# processor_beaglebone.net
KiCad netlist of a schematic drawn in Altium Designer
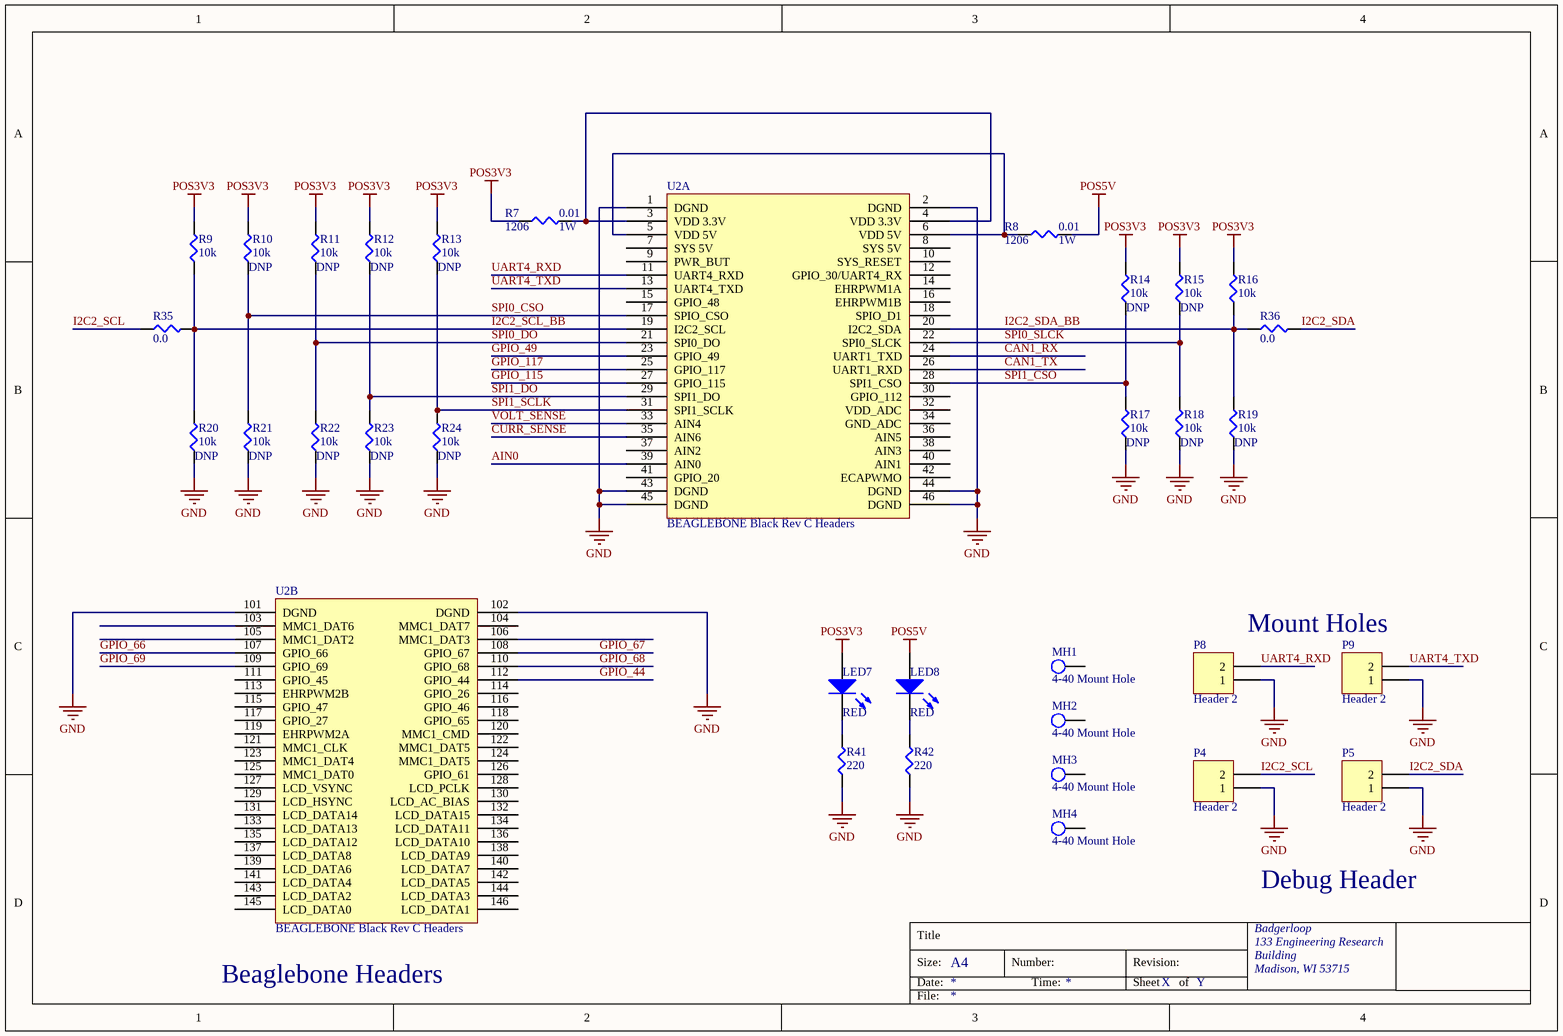
[diagram p0: processor_beaglebone.SchDoc]

(export (version "E")
  (design (tool "Eeschema 10.0.6"))
  (components
    (comp (ref "LED7")
      (value "RED")
      (footprint "LED 0603 RED")
      (description "Red 631nm LED Indication - Discrete 2V 0603 (1608 Metric)")
      (fields (field (name "MANUFACTURER") "Lite-On Inc."))
      (libsource (lib "misc") (part "LED RED 0603"))
    )
    (comp (ref "LED8")
      (value "RED")
      (footprint "LED 0603 RED")
      (description "Red 631nm LED Indication - Discrete 2V 0603 (1608 Metric)")
      (fields (field (name "MANUFACTURER") "Lite-On Inc."))
      (libsource (lib "misc") (part "LED RED 0603"))
    )
    (comp (ref "MH1")
      (value "4-40 Mount Hole")
      (footprint "MH")
      (libsource (lib "misc") (part "4-40 Mount Hole"))
    )
    (comp (ref "MH2")
      (value "4-40 Mount Hole")
      (footprint "MH")
      (libsource (lib "misc") (part "4-40 Mount Hole"))
    )
    (comp (ref "MH3")
      (value "4-40 Mount Hole")
      (footprint "MH")
      (libsource (lib "misc") (part "4-40 Mount Hole"))
    )
    (comp (ref "MH4")
      (value "4-40 Mount Hole")
      (footprint "MH")
      (libsource (lib "misc") (part "4-40 Mount Hole"))
    )
    (comp (ref "P4")
      (value "Header 2")
      (footprint "Pin Header 1x2 TH Pitch 2.54mm")
      (description "Header, 2-Pin")
      (fields (field (name "PUBLISHER") "Altium Limited"))
      (libsource (lib "connector") (part "Header 2"))
    )
    (comp (ref "P5")
      (value "Header 2")
      (footprint "Pin Header 1x2 TH Pitch 2.54mm")
      (description "Header, 2-Pin")
      (fields (field (name "PUBLISHER") "Altium Limited"))
      (libsource (lib "connector") (part "Header 2"))
    )
    (comp (ref "P8")
      (value "Header 2")
      (footprint "Pin Header 1x2 TH Pitch 2.54mm")
      (description "Header, 2-Pin")
      (fields (field (name "PUBLISHER") "Altium Limited"))
      (libsource (lib "connector") (part "Header 2"))
    )
    (comp (ref "P9")
      (value "Header 2")
      (footprint "Pin Header 1x2 TH Pitch 2.54mm")
      (description "Header, 2-Pin")
      (fields (field (name "PUBLISHER") "Altium Limited"))
      (libsource (lib "connector") (part "Header 2"))
    )
    (comp (ref "R7")
      (value "0.01")
      (footprint "SMD-1206-RES")
      (description "RES SMD 0.01 OHM 1% 1W 1206")
      (fields
        (field (name "PART NUMBER") "ERJ-8CWFR010V")
        (field (name "DIGI-KEY PART NUMBER") "P0.01BVCT-ND")
        (field (name "POWER (WATTS)") "1W")
        (field (name "SUPPLIER DEVICE PACKAGE") "1206")
      )
      (libsource (lib "resistor") (part "ERJ-8CWFR010V"))
    )
    (comp (ref "R8")
      (value "0.01")
      (footprint "SMD-1206-RES")
      (description "RES SMD 0.01 OHM 1% 1W 1206")
      (fields
        (field (name "PART NUMBER") "ERJ-8CWFR010V")
        (field (name "DIGI-KEY PART NUMBER") "P0.01BVCT-ND")
        (field (name "POWER (WATTS)") "1W")
        (field (name "SUPPLIER DEVICE PACKAGE") "1206")
      )
      (libsource (lib "resistor") (part "ERJ-8CWFR010V"))
    )
    (comp (ref "R9")
      (value "10k")
      (footprint "SMD-0402-RES")
      (description "RES SMD 10K OHM 5% 1/10W 0402")
      (fields (field (name "PART NUMBER") "ERJ-2GEJ103X") (field (name "DIGI-KEY PART NUMBER") "P10KJCT-ND"))
      (libsource (lib "resistor") (part "ERJ-2GEJ103X"))
    )
    (comp (ref "R10")
      (value "10k")
      (footprint "SMD-0402-RES")
      (description "RES SMD 10K OHM 5% 1/10W 0402")
      (fields
        (field (name "PART NUMBER") "ERJ-2GEJ103X")
        (field (name "DIGI-KEY PART NUMBER") "P10KJCT-ND")
        (field (name "DNP") "DNP")
      )
      (libsource (lib "resistor") (part "ERJ-2GEJ103X"))
    )
    (comp (ref "R11")
      (value "10k")
      (footprint "SMD-0402-RES")
      (description "RES SMD 10K OHM 5% 1/10W 0402")
      (fields
        (field (name "PART NUMBER") "ERJ-2GEJ103X")
        (field (name "DIGI-KEY PART NUMBER") "P10KJCT-ND")
        (field (name "DNP") "DNP")
      )
      (libsource (lib "resistor") (part "ERJ-2GEJ103X"))
    )
    (comp (ref "R12")
      (value "10k")
      (footprint "SMD-0402-RES")
      (description "RES SMD 10K OHM 5% 1/10W 0402")
      (fields
        (field (name "PART NUMBER") "ERJ-2GEJ103X")
        (field (name "DIGI-KEY PART NUMBER") "P10KJCT-ND")
        (field (name "DNP") "DNP")
      )
      (libsource (lib "resistor") (part "ERJ-2GEJ103X"))
    )
    (comp (ref "R13")
      (value "10k")
      (footprint "SMD-0402-RES")
      (description "RES SMD 10K OHM 5% 1/10W 0402")
      (fields
        (field (name "PART NUMBER") "ERJ-2GEJ103X")
        (field (name "DIGI-KEY PART NUMBER") "P10KJCT-ND")
        (field (name "DNP") "DNP")
      )
      (libsource (lib "resistor") (part "ERJ-2GEJ103X"))
    )
    (comp (ref "R14")
      (value "10k")
      (footprint "SMD-0402-RES")
      (description "RES SMD 10K OHM 5% 1/10W 0402")
      (fields
        (field (name "PART NUMBER") "ERJ-2GEJ103X")
        (field (name "DIGI-KEY PART NUMBER") "P10KJCT-ND")
        (field (name "DNP") "DNP")
      )
      (libsource (lib "resistor") (part "ERJ-2GEJ103X"))
    )
    (comp (ref "R15")
      (value "10k")
      (footprint "SMD-0402-RES")
      (description "RES SMD 10K OHM 5% 1/10W 0402")
      (fields
        (field (name "PART NUMBER") "ERJ-2GEJ103X")
        (field (name "DIGI-KEY PART NUMBER") "P10KJCT-ND")
        (field (name "DNP") "DNP")
      )
      (libsource (lib "resistor") (part "ERJ-2GEJ103X"))
    )
    (comp (ref "R16")
      (value "10k")
      (footprint "SMD-0402-RES")
      (description "RES SMD 10K OHM 5% 1/10W 0402")
      (fields (field (name "PART NUMBER") "ERJ-2GEJ103X") (field (name "DIGI-KEY PART NUMBER") "P10KJCT-ND"))
      (libsource (lib "resistor") (part "ERJ-2GEJ103X"))
    )
    (comp (ref "R17")
      (value "10k")
      (footprint "SMD-0402-RES")
      (description "RES SMD 10K OHM 5% 1/10W 0402")
      (fields
        (field (name "PART NUMBER") "ERJ-2GEJ103X")
        (field (name "DIGI-KEY PART NUMBER") "P10KJCT-ND")
        (field (name "DNP") "DNP")
      )
      (libsource (lib "resistor") (part "ERJ-2GEJ103X"))
    )
    (comp (ref "R18")
      (value "10k")
      (footprint "SMD-0402-RES")
      (description "RES SMD 10K OHM 5% 1/10W 0402")
      (fields
        (field (name "PART NUMBER") "ERJ-2GEJ103X")
        (field (name "DIGI-KEY PART NUMBER") "P10KJCT-ND")
        (field (name "DNP") "DNP")
      )
      (libsource (lib "resistor") (part "ERJ-2GEJ103X"))
    )
    (comp (ref "R19")
      (value "10k")
      (footprint "SMD-0402-RES")
      (description "RES SMD 10K OHM 5% 1/10W 0402")
      (fields
        (field (name "PART NUMBER") "ERJ-2GEJ103X")
        (field (name "DIGI-KEY PART NUMBER") "P10KJCT-ND")
        (field (name "DNP") "DNP")
      )
      (libsource (lib "resistor") (part "ERJ-2GEJ103X"))
    )
    (comp (ref "R20")
      (value "10k")
      (footprint "SMD-0402-RES")
      (description "RES SMD 10K OHM 5% 1/10W 0402")
      (fields
        (field (name "PART NUMBER") "ERJ-2GEJ103X")
        (field (name "DIGI-KEY PART NUMBER") "P10KJCT-ND")
        (field (name "DNP") "DNP")
      )
      (libsource (lib "resistor") (part "ERJ-2GEJ103X"))
    )
    (comp (ref "R21")
      (value "10k")
      (footprint "SMD-0402-RES")
      (description "RES SMD 10K OHM 5% 1/10W 0402")
      (fields
        (field (name "PART NUMBER") "ERJ-2GEJ103X")
        (field (name "DIGI-KEY PART NUMBER") "P10KJCT-ND")
        (field (name "DNP") "DNP")
      )
      (libsource (lib "resistor") (part "ERJ-2GEJ103X"))
    )
    (comp (ref "R22")
      (value "10k")
      (footprint "SMD-0402-RES")
      (description "RES SMD 10K OHM 5% 1/10W 0402")
      (fields
        (field (name "PART NUMBER") "ERJ-2GEJ103X")
        (field (name "DIGI-KEY PART NUMBER") "P10KJCT-ND")
        (field (name "DNP") "DNP")
      )
      (libsource (lib "resistor") (part "ERJ-2GEJ103X"))
    )
    (comp (ref "R23")
      (value "10k")
      (footprint "SMD-0402-RES")
      (description "RES SMD 10K OHM 5% 1/10W 0402")
      (fields
        (field (name "PART NUMBER") "ERJ-2GEJ103X")
        (field (name "DIGI-KEY PART NUMBER") "P10KJCT-ND")
        (field (name "DNP") "DNP")
      )
      (libsource (lib "resistor") (part "ERJ-2GEJ103X"))
    )
    (comp (ref "R24")
      (value "10k")
      (footprint "SMD-0402-RES")
      (description "RES SMD 10K OHM 5% 1/10W 0402")
      (fields
        (field (name "PART NUMBER") "ERJ-2GEJ103X")
        (field (name "DIGI-KEY PART NUMBER") "P10KJCT-ND")
        (field (name "DNP") "DNP")
      )
      (libsource (lib "resistor") (part "ERJ-2GEJ103X"))
    )
    (comp (ref "R35")
      (value "0.0")
      (footprint "SMD-0402-RES")
      (description "RES SMD 0.0OHM JUMPER 1/10W 0402")
      (fields (field (name "PART NUMBER") "ERJ-2GE0R00X") (field (name "DIGI-KEY PART NUMBER") "P0.0JCT-ND"))
      (libsource (lib "resistor") (part "ERJ-2GE0R00X"))
    )
    (comp (ref "R36")
      (value "0.0")
      (footprint "SMD-0402-RES")
      (description "RES SMD 0.0OHM JUMPER 1/10W 0402")
      (fields (field (name "PART NUMBER") "ERJ-2GE0R00X") (field (name "DIGI-KEY PART NUMBER") "P0.0JCT-ND"))
      (libsource (lib "resistor") (part "ERJ-2GE0R00X"))
    )
    (comp (ref "R41")
      (value "220")
      (footprint "SMD-0805-RES")
      (description "RES SMD 220 OHM 1% 1/8W 0805")
      (fields (field (name "PART NUMBER") "ERJ-6ENF2200V") (field (name "DIGI-KEY PART NUMBER") "P220CCT-ND"))
      (libsource (lib "resistor") (part "ERJ-6ENF2200V"))
    )
    (comp (ref "R42")
      (value "220")
      (footprint "SMD-0805-RES")
      (description "RES SMD 220 OHM 1% 1/8W 0805")
      (fields (field (name "PART NUMBER") "ERJ-6ENF2200V") (field (name "DIGI-KEY PART NUMBER") "P220CCT-ND"))
      (libsource (lib "resistor") (part "ERJ-6ENF2200V"))
    )
    (comp (ref "U2")
      (value "BEAGLEBONE Black Rev C Headers")
      (footprint "Beaglebone_Topside")
      (description "Beaglebone Black Rev C Header")
      (libsource (lib "temp") (part "Beaglebone"))
    )
  )
  (nets
    (net (code "1") (name "/AIN0") (class "Default")
      (node (ref "U2") (pin "39") (pinfunction "AIN0_39") (pintype "passive"))
    )
    (net (code "2") (name "/CAN1_RX") (class "Default")
      (node (ref "U2") (pin "24") (pinfunction "UART1_TXD_24") (pintype "passive"))
    )
    (net (code "3") (name "/CAN1_TX") (class "Default")
      (node (ref "U2") (pin "26") (pinfunction "UART1_RXD_26") (pintype "passive"))
    )
    (net (code "4") (name "/CURR_SENSE") (class "Default")
      (node (ref "U2") (pin "35") (pinfunction "AIN6_35") (pintype "passive"))
    )
    (net (code "5") (name "/GPIO_44") (class "Default")
      (node (ref "U2") (pin "112") (pinfunction "GPIO_44_112") (pintype "passive"))
    )
    (net (code "6") (name "/GPIO_49") (class "Default")
      (node (ref "U2") (pin "23") (pinfunction "GPIO_49_23") (pintype "passive"))
    )
    (net (code "7") (name "/GPIO_66") (class "Default")
      (node (ref "U2") (pin "107") (pinfunction "GPIO_66_107") (pintype "passive"))
    )
    (net (code "8") (name "/GPIO_67") (class "Default")
      (node (ref "U2") (pin "108") (pinfunction "GPIO_67_108") (pintype "passive"))
    )
    (net (code "9") (name "/GPIO_68") (class "Default")
      (node (ref "U2") (pin "110") (pinfunction "GPIO_68_110") (pintype "passive"))
    )
    (net (code "10") (name "/GPIO_69") (class "Default")
      (node (ref "U2") (pin "109") (pinfunction "GPIO_69_109") (pintype "passive"))
    )
    (net (code "11") (name "/GPIO_115") (class "Default")
      (node (ref "U2") (pin "27") (pinfunction "GPIO_115_27") (pintype "passive"))
    )
    (net (code "12") (name "/GPIO_117") (class "Default")
      (node (ref "U2") (pin "25") (pinfunction "GPIO_117_25") (pintype "passive"))
    )
    (net (code "13") (name "/I2C2_SCL") (class "Default")
      (node (ref "P4") (pin "2") (pinfunction "2_2") (pintype "passive"))
      (node (ref "R35") (pin "1") (pinfunction "1_1") (pintype "passive"))
    )
    (net (code "14") (name "/I2C2_SCL_BB") (class "Default")
      (node (ref "R20") (pin "2") (pinfunction "2_2") (pintype "passive"))
      (node (ref "R35") (pin "2") (pinfunction "2_2") (pintype "passive"))
      (node (ref "R9") (pin "1") (pinfunction "1_1") (pintype "passive"))
      (node (ref "U2") (pin "19") (pinfunction "I2C2_SCL_19") (pintype "passive"))
    )
    (net (code "15") (name "/I2C2_SDA") (class "Default")
      (node (ref "P5") (pin "2") (pinfunction "2_2") (pintype "passive"))
      (node (ref "R36") (pin "2") (pinfunction "2_2") (pintype "passive"))
    )
    (net (code "16") (name "/I2C2_SDA_BB") (class "Default")
      (node (ref "R16") (pin "1") (pinfunction "1_1") (pintype "passive"))
      (node (ref "R19") (pin "2") (pinfunction "2_2") (pintype "passive"))
      (node (ref "R36") (pin "1") (pinfunction "1_1") (pintype "passive"))
      (node (ref "U2") (pin "20") (pinfunction "I2C2_SDA_20") (pintype "passive"))
    )
    (net (code "17") (name "/SPI0_CSO") (class "Default")
      (node (ref "R10") (pin "1") (pinfunction "1_1") (pintype "passive"))
      (node (ref "R21") (pin "2") (pinfunction "2_2") (pintype "passive"))
      (node (ref "U2") (pin "17") (pinfunction "SPIO_CSO_17") (pintype "passive"))
    )
    (net (code "18") (name "/SPI0_DO") (class "Default")
      (node (ref "R11") (pin "1") (pinfunction "1_1") (pintype "passive"))
      (node (ref "R22") (pin "2") (pinfunction "2_2") (pintype "passive"))
      (node (ref "U2") (pin "21") (pinfunction "SPI0_DO_21") (pintype "passive"))
    )
    (net (code "19") (name "/SPI0_SLCK") (class "Default")
      (node (ref "R15") (pin "1") (pinfunction "1_1") (pintype "passive"))
      (node (ref "R18") (pin "2") (pinfunction "2_2") (pintype "passive"))
      (node (ref "U2") (pin "22") (pinfunction "SPI0_SLCK_22") (pintype "passive"))
    )
    (net (code "20") (name "/SPI1_CSO") (class "Default")
      (node (ref "R14") (pin "1") (pinfunction "1_1") (pintype "passive"))
      (node (ref "R17") (pin "2") (pinfunction "2_2") (pintype "passive"))
      (node (ref "U2") (pin "28") (pinfunction "SPI1_CSO_28") (pintype "passive"))
    )
    (net (code "21") (name "/SPI1_DO") (class "Default")
      (node (ref "R12") (pin "1") (pinfunction "1_1") (pintype "passive"))
      (node (ref "R23") (pin "2") (pinfunction "2_2") (pintype "passive"))
      (node (ref "U2") (pin "29") (pinfunction "SPI1_DO_29") (pintype "passive"))
    )
    (net (code "22") (name "/SPI1_SCLK") (class "Default")
      (node (ref "R13") (pin "1") (pinfunction "1_1") (pintype "passive"))
      (node (ref "R24") (pin "2") (pinfunction "2_2") (pintype "passive"))
      (node (ref "U2") (pin "31") (pinfunction "SPI1_SCLK_31") (pintype "passive"))
    )
    (net (code "23") (name "/UART4_RXD") (class "Default")
      (node (ref "P8") (pin "2") (pinfunction "2_2") (pintype "passive"))
      (node (ref "U2") (pin "11") (pinfunction "UART4_RXD_11") (pintype "passive"))
    )
    (net (code "24") (name "/UART4_TXD") (class "Default")
      (node (ref "P9") (pin "2") (pinfunction "2_2") (pintype "passive"))
      (node (ref "U2") (pin "13") (pinfunction "UART4_TXD_13") (pintype "passive"))
    )
    (net (code "25") (name "/VOLT_SENSE") (class "Default")
      (node (ref "U2") (pin "33") (pinfunction "AIN4_33") (pintype "passive"))
    )
    (net (code "26") (name "GND") (class "Default")
      (node (ref "P4") (pin "1") (pinfunction "1_1") (pintype "passive"))
      (node (ref "P5") (pin "1") (pinfunction "1_1") (pintype "passive"))
      (node (ref "P8") (pin "1") (pinfunction "1_1") (pintype "passive"))
      (node (ref "P9") (pin "1") (pinfunction "1_1") (pintype "passive"))
      (node (ref "R17") (pin "1") (pinfunction "1_1") (pintype "passive"))
      (node (ref "R18") (pin "1") (pinfunction "1_1") (pintype "passive"))
      (node (ref "R19") (pin "1") (pinfunction "1_1") (pintype "passive"))
      (node (ref "R20") (pin "1") (pinfunction "1_1") (pintype "passive"))
      (node (ref "R21") (pin "1") (pinfunction "1_1") (pintype "passive"))
      (node (ref "R22") (pin "1") (pinfunction "1_1") (pintype "passive"))
      (node (ref "R23") (pin "1") (pinfunction "1_1") (pintype "passive"))
      (node (ref "R24") (pin "1") (pinfunction "1_1") (pintype "passive"))
      (node (ref "R41") (pin "1") (pinfunction "1_1") (pintype "passive"))
      (node (ref "R42") (pin "1") (pinfunction "1_1") (pintype "passive"))
      (node (ref "U2") (pin "1") (pinfunction "DGND_1") (pintype "passive"))
      (node (ref "U2") (pin "101") (pinfunction "DGND_101") (pintype "passive"))
      (node (ref "U2") (pin "102") (pinfunction "DGND_102") (pintype "passive"))
      (node (ref "U2") (pin "2") (pinfunction "DGND_2") (pintype "passive"))
      (node (ref "U2") (pin "43") (pinfunction "DGND_43") (pintype "passive"))
      (node (ref "U2") (pin "44") (pinfunction "DGND_44") (pintype "passive"))
      (node (ref "U2") (pin "45") (pinfunction "DGND_45") (pintype "passive"))
      (node (ref "U2") (pin "46") (pinfunction "DGND_46") (pintype "passive"))
    )
    (net (code "27") (name "Net-(LED7-K)") (class "Default")
      (node (ref "LED7") (pin "2") (pinfunction "K_2") (pintype "passive"))
      (node (ref "R41") (pin "2") (pinfunction "2_2") (pintype "passive"))
    )
    (net (code "28") (name "Net-(LED8-K)") (class "Default")
      (node (ref "LED8") (pin "2") (pinfunction "K_2") (pintype "passive"))
      (node (ref "R42") (pin "2") (pinfunction "2_2") (pintype "passive"))
    )
    (net (code "29") (name "Net-(R7-Pad2)") (class "Default")
      (node (ref "R7") (pin "2") (pinfunction "2_2") (pintype "passive"))
      (node (ref "U2") (pin "3") (pinfunction "VDD_3.3V_3") (pintype "passive"))
      (node (ref "U2") (pin "4") (pinfunction "VDD_3.3V_4") (pintype "passive"))
    )
    (net (code "30") (name "Net-(R8-Pad1)") (class "Default")
      (node (ref "R8") (pin "1") (pinfunction "1_1") (pintype "passive"))
      (node (ref "U2") (pin "5") (pinfunction "VDD_5V_5") (pintype "passive"))
      (node (ref "U2") (pin "6") (pinfunction "VDD_5V_6") (pintype "passive"))
    )
    (net (code "31") (name "POS3V3") (class "Default")
      (node (ref "LED7") (pin "1") (pinfunction "A_1") (pintype "passive"))
      (node (ref "R10") (pin "2") (pinfunction "2_2") (pintype "passive"))
      (node (ref "R11") (pin "2") (pinfunction "2_2") (pintype "passive"))
      (node (ref "R12") (pin "2") (pinfunction "2_2") (pintype "passive"))
      (node (ref "R13") (pin "2") (pinfunction "2_2") (pintype "passive"))
      (node (ref "R14") (pin "2") (pinfunction "2_2") (pintype "passive"))
      (node (ref "R15") (pin "2") (pinfunction "2_2") (pintype "passive"))
      (node (ref "R16") (pin "2") (pinfunction "2_2") (pintype "passive"))
      (node (ref "R7") (pin "1") (pinfunction "1_1") (pintype "passive"))
      (node (ref "R9") (pin "2") (pinfunction "2_2") (pintype "passive"))
    )
    (net (code "32") (name "POS5V") (class "Default")
      (node (ref "LED8") (pin "1") (pinfunction "A_1") (pintype "passive"))
      (node (ref "R8") (pin "2") (pinfunction "2_2") (pintype "passive"))
    )
    (net (code "33") (name "unconnected-(MH1-Pad46)") (class "Default")
      (node (ref "MH1") (pin "46") (pinfunction "46_46") (pintype "passive"))
    )
    (net (code "34") (name "unconnected-(MH2-Pad46)") (class "Default")
      (node (ref "MH2") (pin "46") (pinfunction "46_46") (pintype "passive"))
    )
    (net (code "35") (name "unconnected-(MH3-Pad46)") (class "Default")
      (node (ref "MH3") (pin "46") (pinfunction "46_46") (pintype "passive"))
    )
    (net (code "36") (name "unconnected-(MH4-Pad46)") (class "Default")
      (node (ref "MH4") (pin "46") (pinfunction "46_46") (pintype "passive"))
    )
    (net (code "37") (name "unconnected-(U2A-AIN1-Pad40)") (class "Default")
      (node (ref "U2") (pin "40") (pinfunction "AIN1_40") (pintype "passive"))
    )
    (net (code "38") (name "unconnected-(U2A-AIN2-Pad37)") (class "Default")
      (node (ref "U2") (pin "37") (pinfunction "AIN2_37") (pintype "passive"))
    )
    (net (code "39") (name "unconnected-(U2A-AIN3-Pad38)") (class "Default")
      (node (ref "U2") (pin "38") (pinfunction "AIN3_38") (pintype "passive"))
    )
    (net (code "40") (name "unconnected-(U2A-AIN5-Pad36)") (class "Default")
      (node (ref "U2") (pin "36") (pinfunction "AIN5_36") (pintype "passive"))
    )
    (net (code "41") (name "unconnected-(U2A-ECAPWMO-Pad42)") (class "Default")
      (node (ref "U2") (pin "42") (pinfunction "ECAPWMO_42") (pintype "passive"))
    )
    (net (code "42") (name "unconnected-(U2A-EHRPWM1A-Pad14)") (class "Default")
      (node (ref "U2") (pin "14") (pinfunction "EHRPWM1A_14") (pintype "passive"))
    )
    (net (code "43") (name "unconnected-(U2A-EHRPWM1B-Pad16)") (class "Default")
      (node (ref "U2") (pin "16") (pinfunction "EHRPWM1B_16") (pintype "passive"))
    )
    (net (code "44") (name "unconnected-(U2A-GND_ADC-Pad34)") (class "Default")
      (node (ref "U2") (pin "34") (pinfunction "GND_ADC_34") (pintype "passive"))
    )
    (net (code "45") (name "unconnected-(U2A-GPIO_20-Pad41)") (class "Default")
      (node (ref "U2") (pin "41") (pinfunction "GPIO_20_41") (pintype "passive"))
    )
    (net (code "46") (name "unconnected-(U2A-GPIO_30{slash}UART4_RX-Pad12)") (class "Default")
      (node (ref "U2") (pin "12") (pinfunction "GPIO_30/UART4_RX_12") (pintype "passive"))
    )
    (net (code "47") (name "unconnected-(U2A-GPIO_48-Pad15)") (class "Default")
      (node (ref "U2") (pin "15") (pinfunction "GPIO_48_15") (pintype "passive"))
    )
    (net (code "48") (name "unconnected-(U2A-GPIO_112-Pad30)") (class "Default")
      (node (ref "U2") (pin "30") (pinfunction "GPIO_112_30") (pintype "passive"))
    )
    (net (code "49") (name "unconnected-(U2A-PWR_BUT-Pad9)") (class "Default")
      (node (ref "U2") (pin "9") (pinfunction "PWR_BUT_9") (pintype "passive"))
    )
    (net (code "50") (name "unconnected-(U2A-SPIO_D1-Pad18)") (class "Default")
      (node (ref "U2") (pin "18") (pinfunction "SPIO_D1_18") (pintype "passive"))
    )
    (net (code "51") (name "unconnected-(U2A-SYS_5V-Pad7)") (class "Default")
      (node (ref "U2") (pin "7") (pinfunction "SYS_5V_7") (pintype "passive"))
    )
    (net (code "52") (name "unconnected-(U2A-SYS_5V-Pad8)") (class "Default")
      (node (ref "U2") (pin "8") (pinfunction "SYS_5V_8") (pintype "passive"))
    )
    (net (code "53") (name "unconnected-(U2A-SYS_RESET-Pad10)") (class "Default")
      (node (ref "U2") (pin "10") (pinfunction "SYS_RESET_10") (pintype "passive"))
    )
    (net (code "54") (name "unconnected-(U2A-VDD_ADC-Pad32)") (class "Default")
      (node (ref "U2") (pin "32") (pinfunction "VDD_ADC_32") (pintype "passive"))
    )
    (net (code "55") (name "unconnected-(U2B-EHRPWM2A-Pad119)") (class "Default")
      (node (ref "U2") (pin "119") (pinfunction "EHRPWM2A_119") (pintype "passive"))
    )
    (net (code "56") (name "unconnected-(U2B-EHRPWM2B-Pad113)") (class "Default")
      (node (ref "U2") (pin "113") (pinfunction "EHRPWM2B_113") (pintype "passive"))
    )
    (net (code "57") (name "unconnected-(U2B-GPIO_26-Pad114)") (class "Default")
      (node (ref "U2") (pin "114") (pinfunction "GPIO_26_114") (pintype "passive"))
    )
    (net (code "58") (name "unconnected-(U2B-GPIO_27-Pad117)") (class "Default")
      (node (ref "U2") (pin "117") (pinfunction "GPIO_27_117") (pintype "passive"))
    )
    (net (code "59") (name "unconnected-(U2B-GPIO_45-Pad111)") (class "Default")
      (node (ref "U2") (pin "111") (pinfunction "GPIO_45_111") (pintype "passive"))
    )
    (net (code "60") (name "unconnected-(U2B-GPIO_46-Pad116)") (class "Default")
      (node (ref "U2") (pin "116") (pinfunction "GPIO_46_116") (pintype "passive"))
    )
    (net (code "61") (name "unconnected-(U2B-GPIO_47-Pad115)") (class "Default")
      (node (ref "U2") (pin "115") (pinfunction "GPIO_47_115") (pintype "passive"))
    )
    (net (code "62") (name "unconnected-(U2B-GPIO_61-Pad126)") (class "Default")
      (node (ref "U2") (pin "126") (pinfunction "GPIO_61_126") (pintype "passive"))
    )
    (net (code "63") (name "unconnected-(U2B-GPIO_65-Pad118)") (class "Default")
      (node (ref "U2") (pin "118") (pinfunction "GPIO_65_118") (pintype "passive"))
    )
    (net (code "64") (name "unconnected-(U2B-LCD_AC_BIAS-Pad130)") (class "Default")
      (node (ref "U2") (pin "130") (pinfunction "LCD_AC_BIAS_130") (pintype "passive"))
    )
    (net (code "65") (name "unconnected-(U2B-LCD_DATA0-Pad145)") (class "Default")
      (node (ref "U2") (pin "145") (pinfunction "LCD_DATA0_145") (pintype "passive"))
    )
    (net (code "66") (name "unconnected-(U2B-LCD_DATA1-Pad146)") (class "Default")
      (node (ref "U2") (pin "146") (pinfunction "LCD_DATA1_146") (pintype "passive"))
    )
    (net (code "67") (name "unconnected-(U2B-LCD_DATA2-Pad143)") (class "Default")
      (node (ref "U2") (pin "143") (pinfunction "LCD_DATA2_143") (pintype "passive"))
    )
    (net (code "68") (name "unconnected-(U2B-LCD_DATA3-Pad144)") (class "Default")
      (node (ref "U2") (pin "144") (pinfunction "LCD_DATA3_144") (pintype "passive"))
    )
    (net (code "69") (name "unconnected-(U2B-LCD_DATA4-Pad141)") (class "Default")
      (node (ref "U2") (pin "141") (pinfunction "LCD_DATA4_141") (pintype "passive"))
    )
    (net (code "70") (name "unconnected-(U2B-LCD_DATA5-Pad142)") (class "Default")
      (node (ref "U2") (pin "142") (pinfunction "LCD_DATA5_142") (pintype "passive"))
    )
    (net (code "71") (name "unconnected-(U2B-LCD_DATA6-Pad139)") (class "Default")
      (node (ref "U2") (pin "139") (pinfunction "LCD_DATA6_139") (pintype "passive"))
    )
    (net (code "72") (name "unconnected-(U2B-LCD_DATA7-Pad140)") (class "Default")
      (node (ref "U2") (pin "140") (pinfunction "LCD_DATA7_140") (pintype "passive"))
    )
    (net (code "73") (name "unconnected-(U2B-LCD_DATA8-Pad137)") (class "Default")
      (node (ref "U2") (pin "137") (pinfunction "LCD_DATA8_137") (pintype "passive"))
    )
    (net (code "74") (name "unconnected-(U2B-LCD_DATA9-Pad138)") (class "Default")
      (node (ref "U2") (pin "138") (pinfunction "LCD_DATA9_138") (pintype "passive"))
    )
    (net (code "75") (name "unconnected-(U2B-LCD_DATA10-Pad136)") (class "Default")
      (node (ref "U2") (pin "136") (pinfunction "LCD_DATA10_136") (pintype "passive"))
    )
    (net (code "76") (name "unconnected-(U2B-LCD_DATA11-Pad134)") (class "Default")
      (node (ref "U2") (pin "134") (pinfunction "LCD_DATA11_134") (pintype "passive"))
    )
    (net (code "77") (name "unconnected-(U2B-LCD_DATA12-Pad135)") (class "Default")
      (node (ref "U2") (pin "135") (pinfunction "LCD_DATA12_135") (pintype "passive"))
    )
    (net (code "78") (name "unconnected-(U2B-LCD_DATA13-Pad133)") (class "Default")
      (node (ref "U2") (pin "133") (pinfunction "LCD_DATA13_133") (pintype "passive"))
    )
    (net (code "79") (name "unconnected-(U2B-LCD_DATA14-Pad131)") (class "Default")
      (node (ref "U2") (pin "131") (pinfunction "LCD_DATA14_131") (pintype "passive"))
    )
    (net (code "80") (name "unconnected-(U2B-LCD_DATA15-Pad132)") (class "Default")
      (node (ref "U2") (pin "132") (pinfunction "LCD_DATA15_132") (pintype "passive"))
    )
    (net (code "81") (name "unconnected-(U2B-LCD_HSYNC-Pad129)") (class "Default")
      (node (ref "U2") (pin "129") (pinfunction "LCD_HSYNC_129") (pintype "passive"))
    )
    (net (code "82") (name "unconnected-(U2B-LCD_PCLK-Pad128)") (class "Default")
      (node (ref "U2") (pin "128") (pinfunction "LCD_PCLK_128") (pintype "passive"))
    )
    (net (code "83") (name "unconnected-(U2B-LCD_VSYNC-Pad127)") (class "Default")
      (node (ref "U2") (pin "127") (pinfunction "LCD_VSYNC_127") (pintype "passive"))
    )
    (net (code "84") (name "unconnected-(U2B-MMC1_CLK-Pad121)") (class "Default")
      (node (ref "U2") (pin "121") (pinfunction "MMC1_CLK_121") (pintype "passive"))
    )
    (net (code "85") (name "unconnected-(U2B-MMC1_CMD-Pad120)") (class "Default")
      (node (ref "U2") (pin "120") (pinfunction "MMC1_CMD_120") (pintype "passive"))
    )
    (net (code "86") (name "unconnected-(U2B-MMC1_DAT0-Pad125)") (class "Default")
      (node (ref "U2") (pin "125") (pinfunction "MMC1_DAT0_125") (pintype "passive"))
    )
    (net (code "87") (name "unconnected-(U2B-MMC1_DAT2-Pad105)") (class "Default")
      (node (ref "U2") (pin "105") (pinfunction "MMC1_DAT2_105") (pintype "passive"))
    )
    (net (code "88") (name "unconnected-(U2B-MMC1_DAT3-Pad106)") (class "Default")
      (node (ref "U2") (pin "106") (pinfunction "MMC1_DAT3_106") (pintype "passive"))
    )
    (net (code "89") (name "unconnected-(U2B-MMC1_DAT4-Pad123)") (class "Default")
      (node (ref "U2") (pin "123") (pinfunction "MMC1_DAT4_123") (pintype "passive"))
    )
    (net (code "90") (name "unconnected-(U2B-MMC1_DAT5-Pad122)") (class "Default")
      (node (ref "U2") (pin "122") (pinfunction "MMC1_DAT5_122") (pintype "passive"))
    )
    (net (code "91") (name "unconnected-(U2B-MMC1_DAT5-Pad124)") (class "Default")
      (node (ref "U2") (pin "124") (pinfunction "MMC1_DAT5_124") (pintype "passive"))
    )
    (net (code "92") (name "unconnected-(U2B-MMC1_DAT6-Pad103)") (class "Default")
      (node (ref "U2") (pin "103") (pinfunction "MMC1_DAT6_103") (pintype "passive"))
    )
    (net (code "93") (name "unconnected-(U2B-MMC1_DAT7-Pad104)") (class "Default")
      (node (ref "U2") (pin "104") (pinfunction "MMC1_DAT7_104") (pintype "passive"))
    )
  )
)
